# base_pcb.net
KiCad netlist of a schematic drawn in EasyEDA Pro
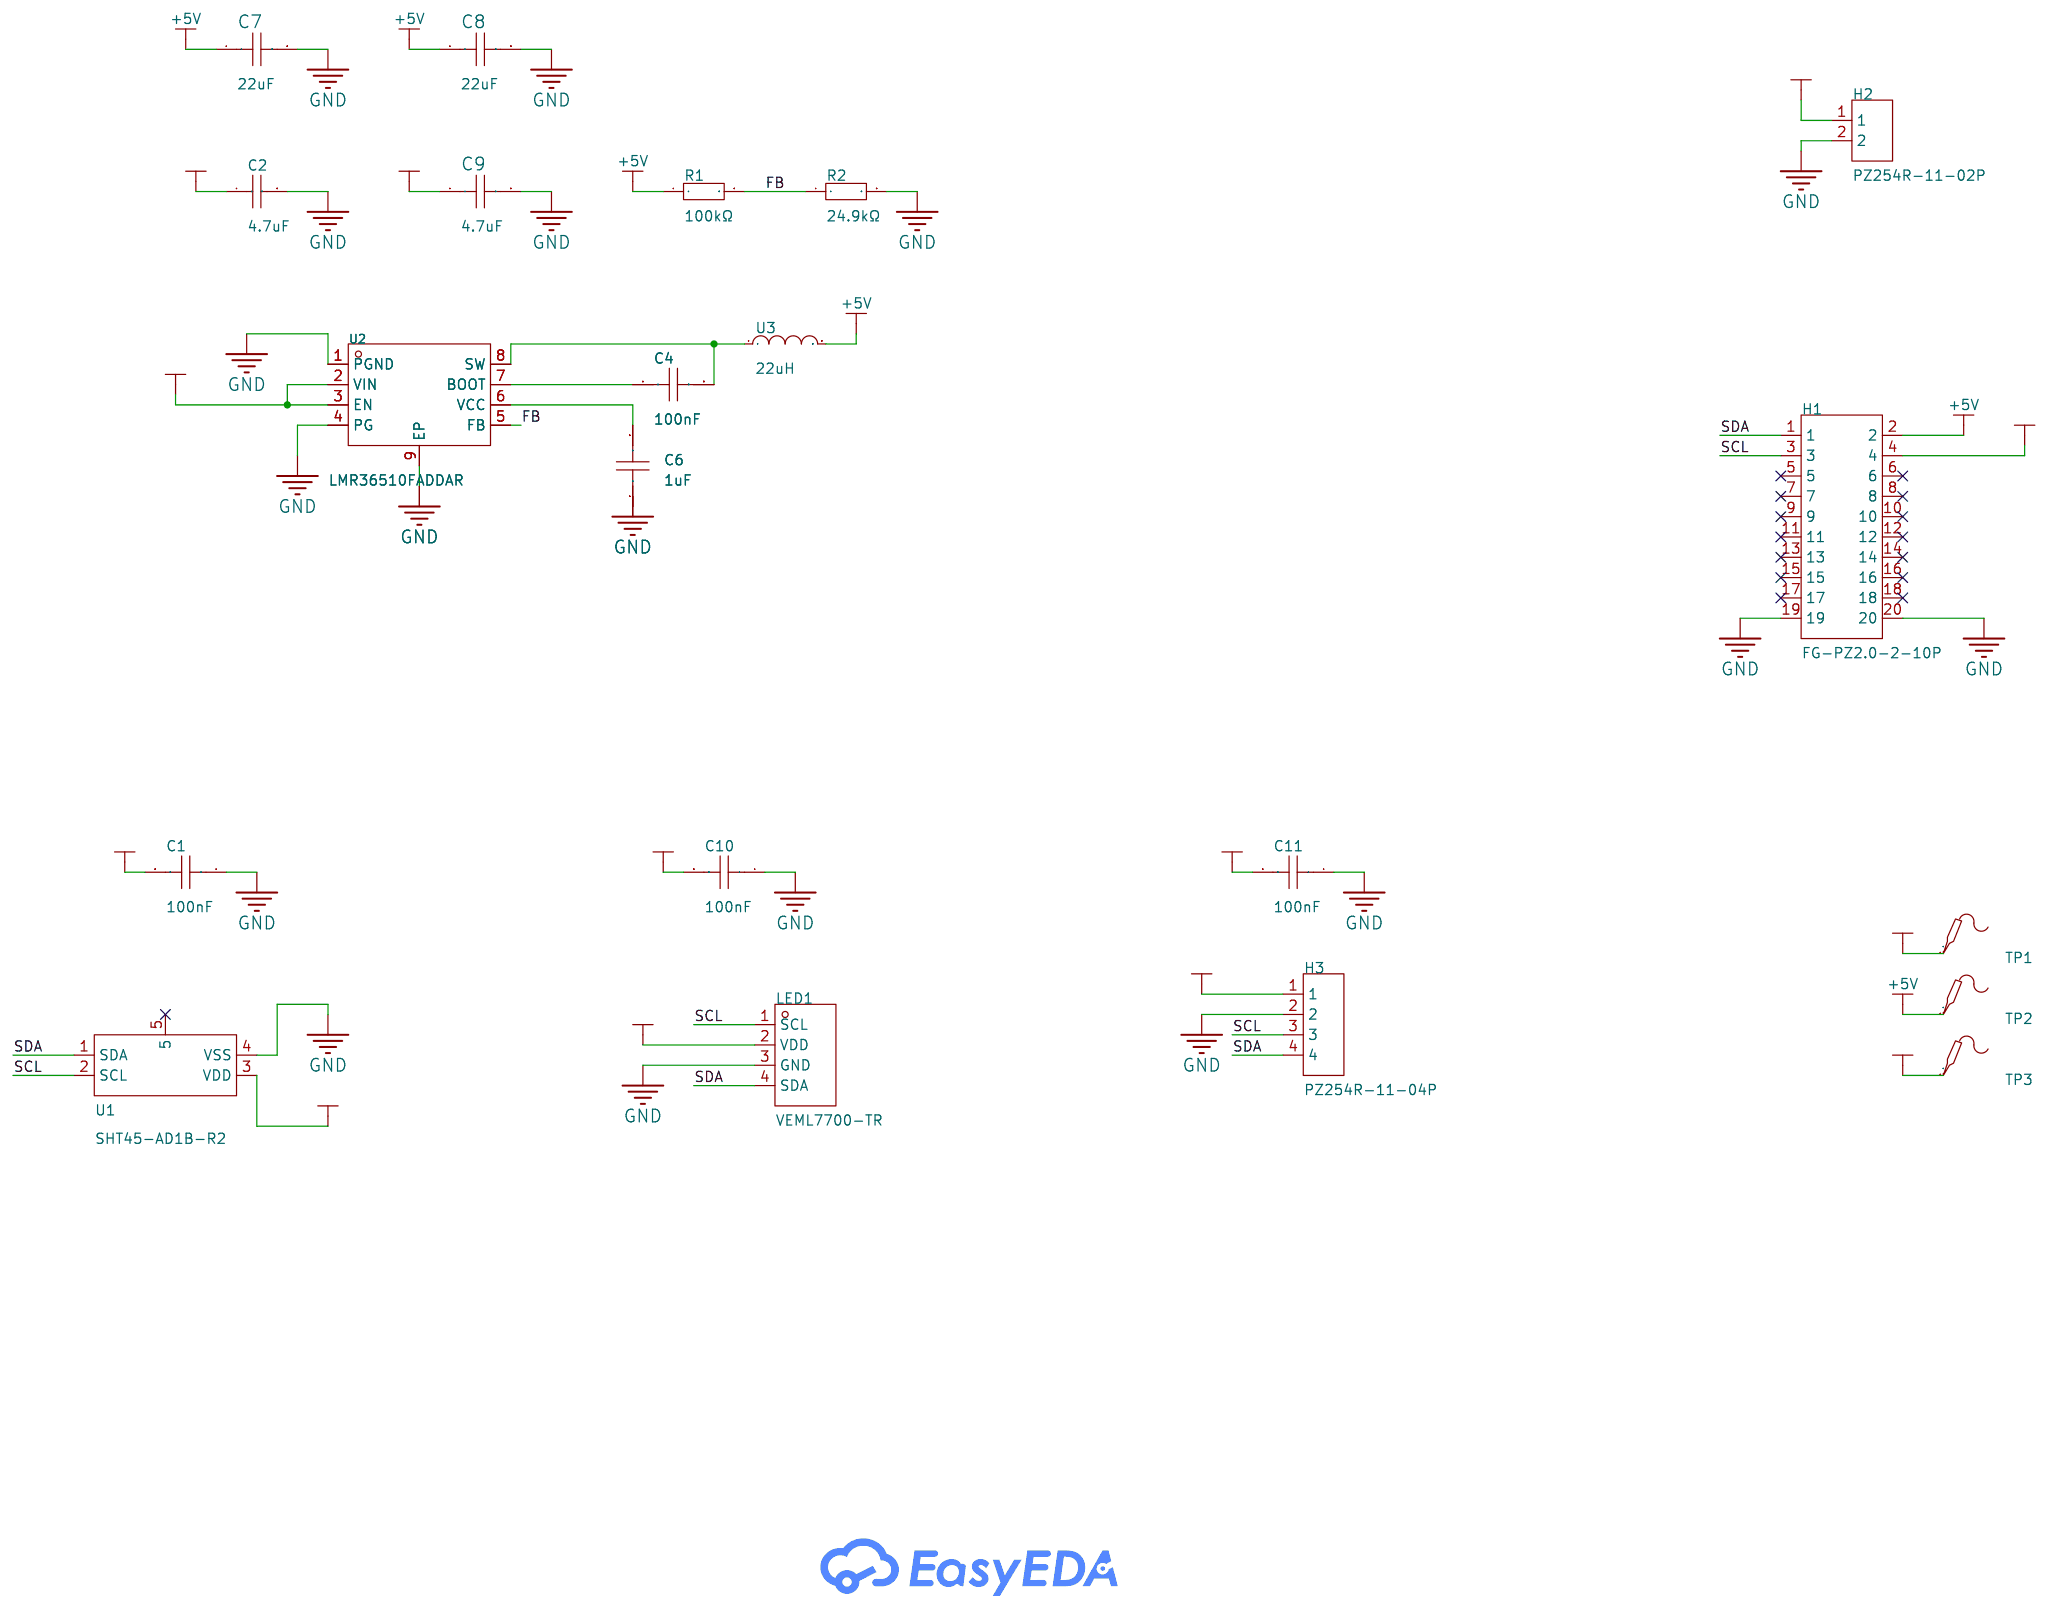
[diagram p0: schematic sheet]

(export (version "E")
  (design (tool "Eeschema 10.0.6"))
  (components
    (comp (ref "C1")
      (value "100nF")
      (footprint "easyedapro:C0201")
      (description "Capacitance:100nF Tolerance:±10% Tolerance:±10% Voltage Rating:50V Temperature Coefficient:X7R")
      (fields
        (field (name "Manufacturer Part") "CC0603KRX7R9BB104")
        (field (name "Manufacturer") "YAGEO(国巨)")
      )
      (libsource (lib "easyedapro") (part "CAP"))
    )
    (comp (ref "C2")
      (value "4.7uF")
      (footprint "easyedapro:C1206")
      (description "Capacitance:4.7uF Tolerance:±10% Tolerance:±10% Voltage Rating:50V Temperature Coefficient:X7R")
      (fields
        (field (name "Manufacturer Part") "CL31B475KBHNNNE")
        (field (name "Manufacturer") "SAMSUNG(三星)")
      )
      (libsource (lib "easyedapro") (part "CL31B475KBHNNNE"))
    )
    (comp (ref "C4")
      (value "100nF")
      (footprint "easyedapro:C0603")
      (description "Capacitance:100nF Tolerance:±10% Tolerance:±10% Voltage Rating:50V Temperature Coefficient:X7R")
      (fields
        (field (name "Manufacturer Part") "CC0603KRX7R9BB104")
        (field (name "Manufacturer") "YAGEO(国巨)")
      )
      (libsource (lib "easyedapro") (part "CC0603KRX7R9BB104"))
    )
    (comp (ref "C6")
      (value "1uF")
      (footprint "easyedapro:C0603")
      (description "Capacitance:1uF Tolerance:±10% Tolerance:±10% Voltage Rating:50V Temperature Coefficient:X5R")
      (fields
        (field (name "Manufacturer Part") "CL10A105KB8NNNC")
        (field (name "Manufacturer") "SAMSUNG(三星)")
      )
      (libsource (lib "easyedapro") (part "CL10A105KB8NNNC"))
    )
    (comp (ref "C7")
      (value "22uF")
      (description "Capacitance:22uF Tolerance:±10% Tolerance:±10% Voltage Rating:25V Temperature Coefficient:X7R")
      (fields
        (field (name "Manufacturer Part") "GRM32ER71E226KE15L")
        (field (name "Manufacturer") "muRata(村田)")
      )
      (libsource (lib "easyedapro") (part "GRM32ER71E226KE15L"))
    )
    (comp (ref "C8")
      (value "22uF")
      (description "Capacitance:22uF Tolerance:±10% Tolerance:±10% Voltage Rating:25V Temperature Coefficient:X7R")
      (fields
        (field (name "Manufacturer Part") "GRM32ER71E226KE15L")
        (field (name "Manufacturer") "muRata(村田)")
      )
      (libsource (lib "easyedapro") (part "GRM32ER71E226KE15L"))
    )
    (comp (ref "C9")
      (value "4.7uF")
      (description "Capacitance:4.7uF Tolerance:±10% Tolerance:±10% Voltage Rating:50V Temperature Coefficient:X7R")
      (fields
        (field (name "Manufacturer Part") "GRM32ER71H475KA88L")
        (field (name "Manufacturer") "muRata(村田)")
      )
      (libsource (lib "easyedapro") (part "GRM32ER71H475KA88L"))
    )
    (comp (ref "C10")
      (value "100nF")
      (footprint "easyedapro:C0201")
      (description "Capacitance:100nF Tolerance:±10% Tolerance:±10% Voltage Rating:50V Temperature Coefficient:X7R")
      (fields
        (field (name "Manufacturer Part") "CC0603KRX7R9BB104")
        (field (name "Manufacturer") "YAGEO(国巨)")
      )
      (libsource (lib "easyedapro") (part "CAP"))
    )
    (comp (ref "C11")
      (value "100nF")
      (footprint "easyedapro:C0201")
      (description "Capacitance:100nF Tolerance:±10% Tolerance:±10% Voltage Rating:50V Temperature Coefficient:X7R")
      (fields
        (field (name "Manufacturer Part") "CC0603KRX7R9BB104")
        (field (name "Manufacturer") "YAGEO(国巨)")
      )
      (libsource (lib "easyedapro") (part "CAP"))
    )
    (comp (ref "H1")
      (value "FG-PZ2.0-2-10P")
      (footprint "easyedapro:HDR-TH_20P-P2.00-V-M-R2-C10-S2.0")
      (fields (field (name "Manufacturer") "FG(富港)"))
      (libsource (lib "easyedapro") (part "FG-PZ2.0-2-10P"))
    )
    (comp (ref "H2")
      (value "PZ254R-11-02P")
      (footprint "easyedapro:HDR-TH_2P-P2.54-H-M-W10.4")
      (fields (field (name "Manufacturer") "XFCN(兴飞)"))
      (libsource (lib "easyedapro") (part "PZ254R-11-02P"))
    )
    (comp (ref "H3")
      (value "PZ254R-11-04P")
      (footprint "easyedapro:HDR-TH_4P-P2.54-H-M-W10.4")
      (fields (field (name "Manufacturer") "XFCN(兴飞)"))
      (libsource (lib "easyedapro") (part "PZ254R-11-04P"))
    )
    (comp (ref "LED1")
      (value "VEML7700-TR")
      (footprint "easyedapro:LED-SMD_4P-L6.8-W2.4_VEML7700-TR")
      (fields (field (name "Manufacturer") "VISHAY(威世)"))
      (libsource (lib "easyedapro") (part "VEML7700-TR"))
    )
    (comp (ref "R1")
      (value "100kΩ")
      (footprint "easyedapro:R0603")
      (fields
        (field (name "Manufacturer Part") "0603WAF1003T5E")
        (field (name "Manufacturer") "UNI-ROYAL(厚声)")
      )
      (libsource (lib "easyedapro") (part "Res"))
    )
    (comp (ref "R2")
      (value "24.9kΩ")
      (footprint "easyedapro:R0603")
      (fields
        (field (name "Manufacturer Part") "0603WAF2492T5E")
        (field (name "Manufacturer") "UNI-ROYAL(厚声)")
      )
      (libsource (lib "easyedapro") (part "Res"))
    )
    (comp (ref "TP1")
      (value "~")
      (footprint "easyedapro:Test-Point-0.5mm")
      (description "Test Point 测试点")
      (libsource (lib "easyedapro") (part "Test-Point"))
    )
    (comp (ref "TP2")
      (value "~")
      (footprint "easyedapro:Test-Point-0.5mm")
      (description "Test Point 测试点")
      (libsource (lib "easyedapro") (part "Test-Point"))
    )
    (comp (ref "TP3")
      (value "~")
      (footprint "easyedapro:Test-Point-0.5mm")
      (description "Test Point 测试点")
      (libsource (lib "easyedapro") (part "Test-Point"))
    )
    (comp (ref "U1")
      (value "SHT45-AD1B-R2")
      (footprint "easyedapro:DFN-4_L1.5-W1.5-P0.8-TL-EP")
      (fields (field (name "Manufacturer") "Sensirion(瑞士盛思锐)"))
      (libsource (lib "easyedapro") (part "SHT45-AD1B-R2"))
    )
    (comp (ref "U2")
      (value "LMR36510FADDAR")
      (footprint "easyedapro:ESOP-8_L4.9-W3.9-P1.27-LS6.0-BL-EP-1")
      (fields (field (name "Manufacturer") "TI(德州仪器)"))
      (libsource (lib "easyedapro") (part "LMR36510FADDAR"))
    )
    (comp (ref "U3")
      (value "22uH")
      (footprint "easyedapro:IND-SMD_L7.1-W6.6")
      (fields (field (name "Manufacturer Part") "APH0630T220M") (field (name "Manufacturer") "APV(爱普微)"))
      (libsource (lib "easyedapro") (part "APH0630T220M"))
    )
  )
  (nets
    (net (code "1") (name "+5V") (class "Default")
      (node (ref "C7") (pin "1") (pinfunction "1_1") (pintype "input"))
      (node (ref "C8") (pin "1") (pinfunction "1_1") (pintype "input"))
      (node (ref "H1") (pin "2") (pinfunction "2_2") (pintype "unspecified"))
      (node (ref "R1") (pin "1") (pinfunction "1_1") (pintype "input"))
      (node (ref "TP2") (pin "1") (pinfunction "1_1") (pintype "unspecified"))
      (node (ref "U3") (pin "2") (pinfunction "2_2") (pintype "unspecified"))
    )
    (net (code "2") (name "+24V") (class "Default")
      (node (ref "C2") (pin "1") (pinfunction "1_1") (pintype "input"))
      (node (ref "C9") (pin "1") (pinfunction "1_1") (pintype "input"))
      (node (ref "H2") (pin "1") (pinfunction "1_1") (pintype "unspecified"))
      (node (ref "TP1") (pin "1") (pinfunction "1_1") (pintype "unspecified"))
      (node (ref "U2") (pin "2") (pinfunction "VIN_2") (pintype "input"))
      (node (ref "U2") (pin "3") (pinfunction "EN_3") (pintype "input"))
    )
    (net (code "3") (name "/FB") (class "Default")
      (node (ref "R1") (pin "2") (pinfunction "2_2") (pintype "input"))
      (node (ref "R2") (pin "1") (pinfunction "1_1") (pintype "input"))
      (node (ref "U2") (pin "5") (pinfunction "FB_5") (pintype "input"))
    )
    (net (code "4") (name "/SCL") (class "Default")
      (node (ref "H1") (pin "3") (pinfunction "3_3") (pintype "unspecified"))
      (node (ref "H3") (pin "3") (pinfunction "3_3") (pintype "unspecified"))
      (node (ref "LED1") (pin "1") (pinfunction "SCL_1") (pintype "unspecified"))
      (node (ref "U1") (pin "2") (pinfunction "SCL_2") (pintype "unspecified"))
    )
    (net (code "5") (name "/SDA") (class "Default")
      (node (ref "H1") (pin "1") (pinfunction "1_1") (pintype "unspecified"))
      (node (ref "H3") (pin "4") (pinfunction "4_4") (pintype "unspecified"))
      (node (ref "LED1") (pin "4") (pinfunction "SDA_4") (pintype "unspecified"))
      (node (ref "U1") (pin "1") (pinfunction "SDA_1") (pintype "unspecified"))
    )
    (net (code "6") (name "3V3") (class "Default")
      (node (ref "C1") (pin "2") (pinfunction "2_2") (pintype "input"))
      (node (ref "C10") (pin "2") (pinfunction "2_2") (pintype "input"))
      (node (ref "C11") (pin "2") (pinfunction "2_2") (pintype "input"))
      (node (ref "H1") (pin "4") (pinfunction "4_4") (pintype "unspecified"))
      (node (ref "H3") (pin "1") (pinfunction "1_1") (pintype "unspecified"))
      (node (ref "LED1") (pin "2") (pinfunction "VDD_2") (pintype "unspecified"))
      (node (ref "TP3") (pin "1") (pinfunction "1_1") (pintype "unspecified"))
      (node (ref "U1") (pin "3") (pinfunction "VDD_3") (pintype "unspecified"))
    )
    (net (code "7") (name "GND") (class "Default")
      (node (ref "C1") (pin "1") (pinfunction "1_1") (pintype "input"))
      (node (ref "C10") (pin "1") (pinfunction "1_1") (pintype "input"))
      (node (ref "C11") (pin "1") (pinfunction "1_1") (pintype "input"))
      (node (ref "C2") (pin "2") (pinfunction "2_2") (pintype "input"))
      (node (ref "C6") (pin "1") (pinfunction "1_1") (pintype "unspecified"))
      (node (ref "C7") (pin "2") (pinfunction "2_2") (pintype "input"))
      (node (ref "C8") (pin "2") (pinfunction "2_2") (pintype "input"))
      (node (ref "C9") (pin "2") (pinfunction "2_2") (pintype "input"))
      (node (ref "H1") (pin "19") (pinfunction "19_19") (pintype "unspecified"))
      (node (ref "H1") (pin "20") (pinfunction "20_20") (pintype "unspecified"))
      (node (ref "H2") (pin "2") (pinfunction "2_2") (pintype "unspecified"))
      (node (ref "H3") (pin "2") (pinfunction "2_2") (pintype "unspecified"))
      (node (ref "LED1") (pin "3") (pinfunction "GND_3") (pintype "unspecified"))
      (node (ref "R2") (pin "2") (pinfunction "2_2") (pintype "input"))
      (node (ref "U1") (pin "4") (pinfunction "VSS_4") (pintype "unspecified"))
      (node (ref "U2") (pin "1") (pinfunction "PGND_1") (pintype "input"))
      (node (ref "U2") (pin "4") (pinfunction "PG_4") (pintype "input"))
      (node (ref "U2") (pin "9") (pinfunction "EP_9") (pintype "input"))
    )
    (net (code "8") (name "Net-(U2-BOOT)") (class "Default")
      (node (ref "C4") (pin "1") (pinfunction "1_1") (pintype "unspecified"))
      (node (ref "U2") (pin "7") (pinfunction "BOOT_7") (pintype "input"))
    )
    (net (code "9") (name "Net-(U2-SW)") (class "Default")
      (node (ref "C4") (pin "2") (pinfunction "2_2") (pintype "unspecified"))
      (node (ref "U2") (pin "8") (pinfunction "SW_8") (pintype "input"))
      (node (ref "U3") (pin "1") (pinfunction "1_1") (pintype "unspecified"))
    )
    (net (code "10") (name "Net-(U2-VCC)") (class "Default")
      (node (ref "C6") (pin "2") (pinfunction "2_2") (pintype "unspecified"))
      (node (ref "U2") (pin "6") (pinfunction "VCC_6") (pintype "input"))
    )
    (net (code "11") (name "unconnected-(H1-Pad5)") (class "Default")
      (node (ref "H1") (pin "5") (pinfunction "5_5") (pintype "unspecified+no_connect"))
    )
    (net (code "12") (name "unconnected-(H1-Pad6)") (class "Default")
      (node (ref "H1") (pin "6") (pinfunction "6_6") (pintype "unspecified+no_connect"))
    )
    (net (code "13") (name "unconnected-(H1-Pad7)") (class "Default")
      (node (ref "H1") (pin "7") (pinfunction "7_7") (pintype "unspecified+no_connect"))
    )
    (net (code "14") (name "unconnected-(H1-Pad8)") (class "Default")
      (node (ref "H1") (pin "8") (pinfunction "8_8") (pintype "unspecified+no_connect"))
    )
    (net (code "15") (name "unconnected-(H1-Pad9)") (class "Default")
      (node (ref "H1") (pin "9") (pinfunction "9_9") (pintype "unspecified+no_connect"))
    )
    (net (code "16") (name "unconnected-(H1-Pad10)") (class "Default")
      (node (ref "H1") (pin "10") (pinfunction "10_10") (pintype "unspecified+no_connect"))
    )
    (net (code "17") (name "unconnected-(H1-Pad11)") (class "Default")
      (node (ref "H1") (pin "11") (pinfunction "11_11") (pintype "unspecified+no_connect"))
    )
    (net (code "18") (name "unconnected-(H1-Pad12)") (class "Default")
      (node (ref "H1") (pin "12") (pinfunction "12_12") (pintype "unspecified+no_connect"))
    )
    (net (code "19") (name "unconnected-(H1-Pad13)") (class "Default")
      (node (ref "H1") (pin "13") (pinfunction "13_13") (pintype "unspecified+no_connect"))
    )
    (net (code "20") (name "unconnected-(H1-Pad14)") (class "Default")
      (node (ref "H1") (pin "14") (pinfunction "14_14") (pintype "unspecified+no_connect"))
    )
    (net (code "21") (name "unconnected-(H1-Pad15)") (class "Default")
      (node (ref "H1") (pin "15") (pinfunction "15_15") (pintype "unspecified+no_connect"))
    )
    (net (code "22") (name "unconnected-(H1-Pad16)") (class "Default")
      (node (ref "H1") (pin "16") (pinfunction "16_16") (pintype "unspecified+no_connect"))
    )
    (net (code "23") (name "unconnected-(H1-Pad17)") (class "Default")
      (node (ref "H1") (pin "17") (pinfunction "17_17") (pintype "unspecified+no_connect"))
    )
    (net (code "24") (name "unconnected-(H1-Pad18)") (class "Default")
      (node (ref "H1") (pin "18") (pinfunction "18_18") (pintype "unspecified+no_connect"))
    )
    (net (code "25") (name "unconnected-(U1-Pad5)") (class "Default")
      (node (ref "U1") (pin "5") (pinfunction "5_5") (pintype "unspecified+no_connect"))
    )
  )
)
